# Segliment_Display.net
KiCad netlist of a schematic drawn in EAGLE
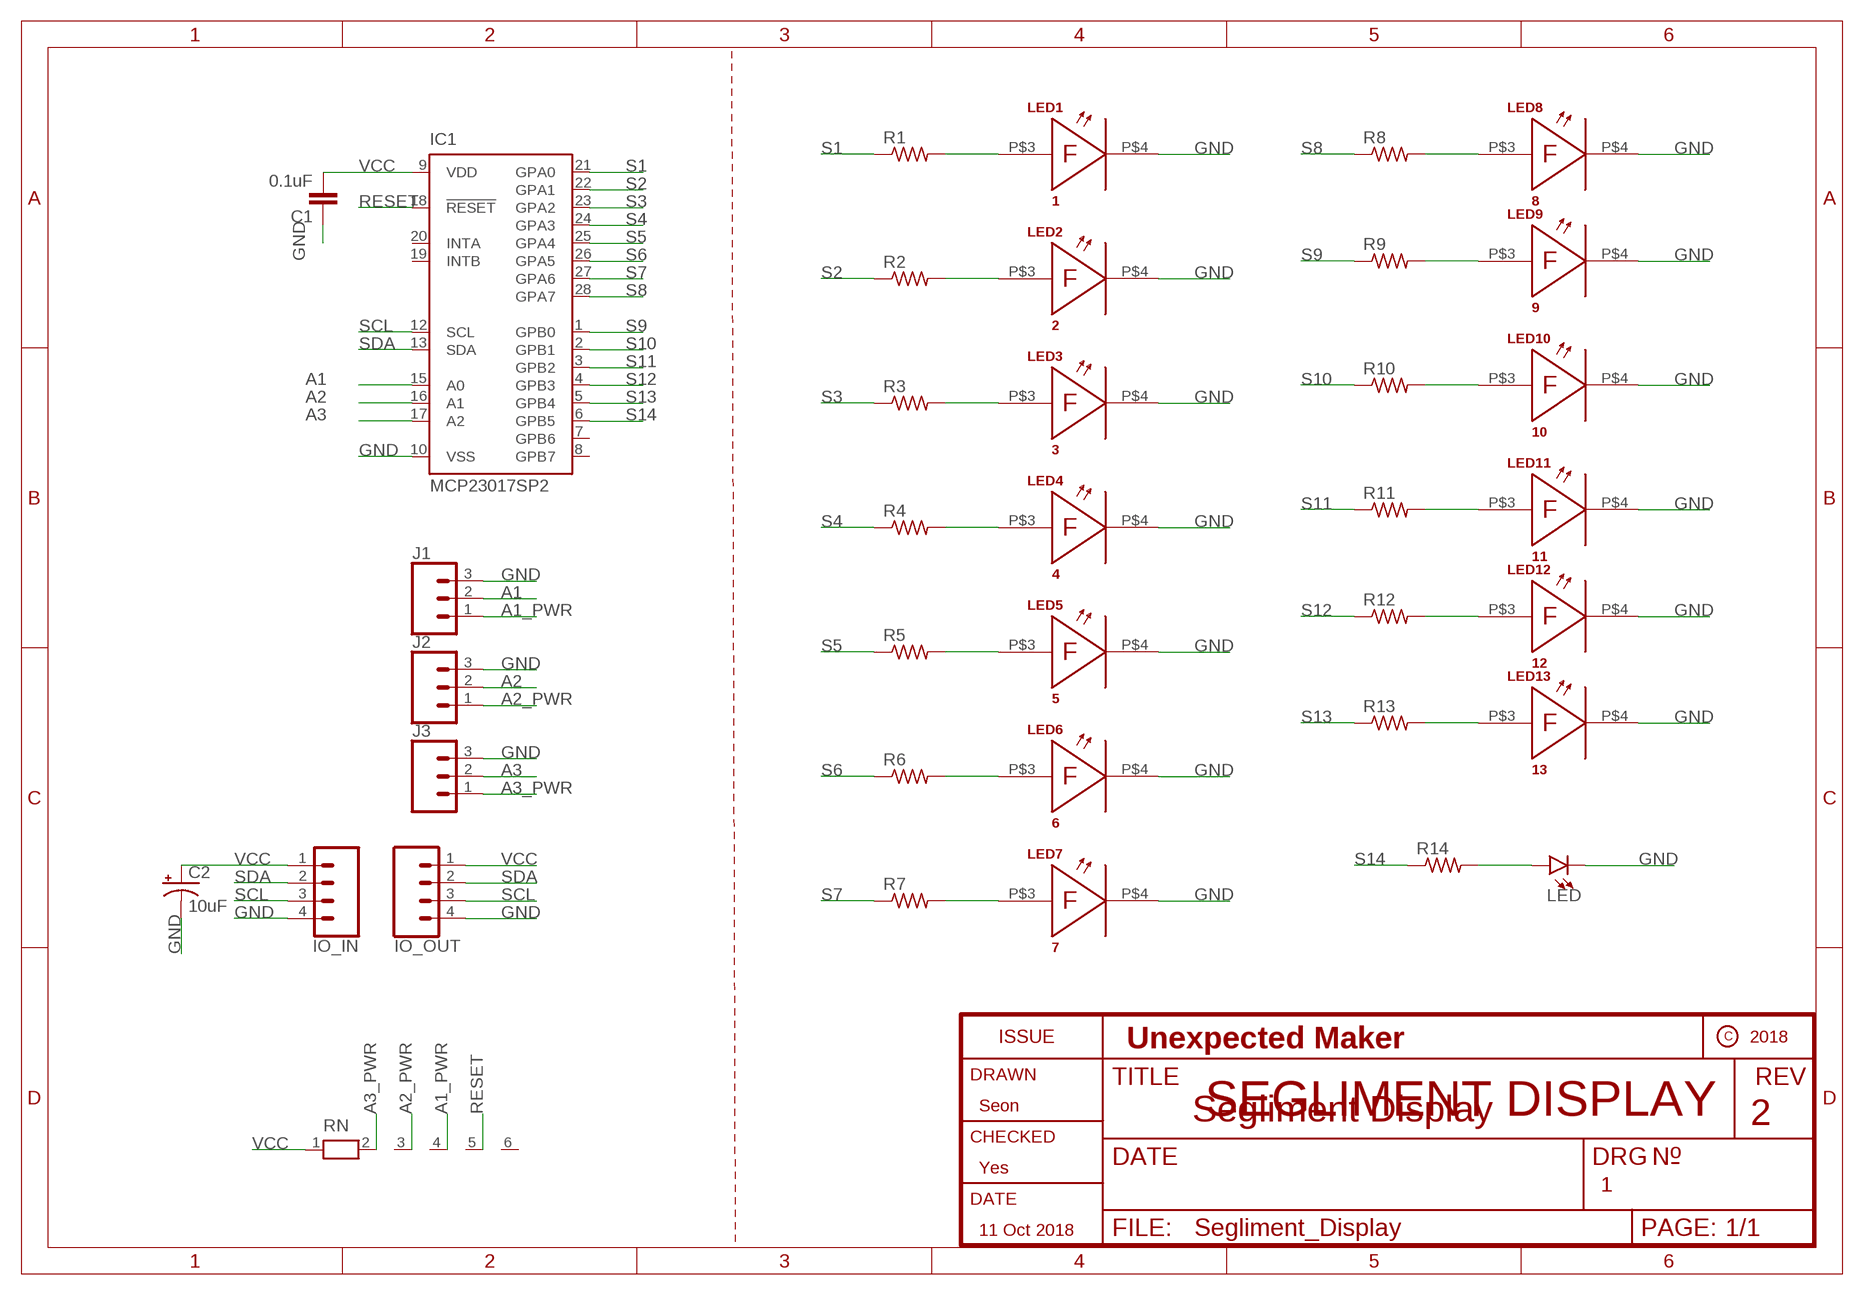
[diagram p0: schematic, sheet 1]

(export (version "E")
  (design (tool "Eeschema 10.0.6"))
  (components
    (comp (ref "C1")
      (value "0.1uF")
      (footprint "eagle-import:CAP-PTH-SMALL-KIT")
      (libsource (lib "eagle-import") (part "0.1UF-KIT-EZ-50V-20%"))
    )
    (comp (ref "C2")
      (value "10uF")
      (footprint "eagle-import:CPOL-RADIAL-2.5MM-5MM")
      (libsource (lib "eagle-import") (part "10UF-POLAR-RADIAL-2.5MM-25V-20%"))
    )
    (comp (ref "IC1")
      (value "MCP23017SP2")
      (footprint "eagle-import:DIL28-3-ROUND")
      (libsource (lib "eagle-import") (part "MCP23017SP2"))
    )
    (comp (ref "IO_IN")
      (value "CONN_041X04_NO_SILK")
      (footprint "eagle-import:1X04_NO_SILK")
      (libsource (lib "eagle-import") (part "CONN_041X04_NO_SILK"))
    )
    (comp (ref "IO_OUT")
      (value "CONN_041X04_NO_SILK")
      (footprint "eagle-import:1X04_NO_SILK")
      (libsource (lib "eagle-import") (part "CONN_041X04_NO_SILK"))
    )
    (comp (ref "J1")
      (value "CONN_031X03_NO_SILK")
      (footprint "eagle-import:1X03_NO_SILK")
      (libsource (lib "eagle-import") (part "CONN_031X03_NO_SILK"))
    )
    (comp (ref "J2")
      (value "CONN_031X03_NO_SILK")
      (footprint "eagle-import:1X03_NO_SILK")
      (libsource (lib "eagle-import") (part "CONN_031X03_NO_SILK"))
    )
    (comp (ref "J3")
      (value "CONN_031X03_NO_SILK")
      (footprint "eagle-import:1X03_NO_SILK")
      (libsource (lib "eagle-import") (part "CONN_031X03_NO_SILK"))
    )
    (comp (ref "LED")
      (value "LED3MM")
      (footprint "eagle-import:LED_3MM")
      (libsource (lib "eagle-import") (part "LED3MM"))
    )
    (comp (ref "LED1")
      (value "1")
      (footprint "eagle-import:RAISED")
      (libsource (lib "eagle-import") (part "LED28-30MMRAISED"))
    )
    (comp (ref "LED2")
      (value "2")
      (footprint "eagle-import:RAISED")
      (libsource (lib "eagle-import") (part "LED28-30MMRAISED"))
    )
    (comp (ref "LED3")
      (value "3")
      (footprint "eagle-import:RAISED")
      (libsource (lib "eagle-import") (part "LED28-30MMRAISED"))
    )
    (comp (ref "LED4")
      (value "4")
      (footprint "eagle-import:RAISED")
      (libsource (lib "eagle-import") (part "LED28-30MMRAISED"))
    )
    (comp (ref "LED5")
      (value "5")
      (footprint "eagle-import:RAISED")
      (libsource (lib "eagle-import") (part "LED28-30MMRAISED"))
    )
    (comp (ref "LED6")
      (value "6")
      (footprint "eagle-import:RAISED")
      (libsource (lib "eagle-import") (part "LED28-30MMRAISED"))
    )
    (comp (ref "LED7")
      (value "7")
      (footprint "eagle-import:RAISED")
      (libsource (lib "eagle-import") (part "LED28-30MMRAISED"))
    )
    (comp (ref "LED8")
      (value "8")
      (footprint "eagle-import:RAISED")
      (libsource (lib "eagle-import") (part "LED28-30MMRAISED"))
    )
    (comp (ref "LED9")
      (value "9")
      (footprint "eagle-import:RAISED")
      (libsource (lib "eagle-import") (part "LED28-30MMRAISED"))
    )
    (comp (ref "LED10")
      (value "10")
      (footprint "eagle-import:RAISED")
      (libsource (lib "eagle-import") (part "LED28-30MMRAISED"))
    )
    (comp (ref "LED11")
      (value "11")
      (footprint "eagle-import:RAISED")
      (libsource (lib "eagle-import") (part "LED28-30MMRAISED"))
    )
    (comp (ref "LED12")
      (value "12")
      (footprint "eagle-import:RAISED")
      (libsource (lib "eagle-import") (part "LED28-30MMRAISED"))
    )
    (comp (ref "LED13")
      (value "13")
      (footprint "eagle-import:RAISED")
      (libsource (lib "eagle-import") (part "LED28-30MMRAISED"))
    )
    (comp (ref "R1")
      (value "R-US_0207/7")
      (footprint "eagle-import:0207_7")
      (libsource (lib "eagle-import") (part "R-US_0207/7"))
    )
    (comp (ref "R2")
      (value "R-US_0207/7")
      (footprint "eagle-import:0207_7")
      (libsource (lib "eagle-import") (part "R-US_0207/7"))
    )
    (comp (ref "R3")
      (value "R-US_0207/7")
      (footprint "eagle-import:0207_7")
      (libsource (lib "eagle-import") (part "R-US_0207/7"))
    )
    (comp (ref "R4")
      (value "R-US_0207/7")
      (footprint "eagle-import:0207_7")
      (libsource (lib "eagle-import") (part "R-US_0207/7"))
    )
    (comp (ref "R5")
      (value "R-US_0207/7")
      (footprint "eagle-import:0207_7")
      (libsource (lib "eagle-import") (part "R-US_0207/7"))
    )
    (comp (ref "R6")
      (value "R-US_0207/7")
      (footprint "eagle-import:0207_7")
      (libsource (lib "eagle-import") (part "R-US_0207/7"))
    )
    (comp (ref "R7")
      (value "R-US_0207/7")
      (footprint "eagle-import:0207_7")
      (libsource (lib "eagle-import") (part "R-US_0207/7"))
    )
    (comp (ref "R8")
      (value "R-US_0207/7")
      (footprint "eagle-import:0207_7")
      (libsource (lib "eagle-import") (part "R-US_0207/7"))
    )
    (comp (ref "R9")
      (value "R-US_0207/7")
      (footprint "eagle-import:0207_7")
      (libsource (lib "eagle-import") (part "R-US_0207/7"))
    )
    (comp (ref "R10")
      (value "R-US_0207/7")
      (footprint "eagle-import:0207_7")
      (libsource (lib "eagle-import") (part "R-US_0207/7"))
    )
    (comp (ref "R11")
      (value "R-US_0207/7")
      (footprint "eagle-import:0207_7")
      (libsource (lib "eagle-import") (part "R-US_0207/7"))
    )
    (comp (ref "R12")
      (value "R-US_0207/7")
      (footprint "eagle-import:0207_7")
      (libsource (lib "eagle-import") (part "R-US_0207/7"))
    )
    (comp (ref "R13")
      (value "R-US_0207/7")
      (footprint "eagle-import:0207_7")
      (libsource (lib "eagle-import") (part "R-US_0207/7"))
    )
    (comp (ref "R14")
      (value "R-US_0207/7")
      (footprint "eagle-import:0207_7")
      (libsource (lib "eagle-import") (part "R-US_0207/7"))
    )
    (comp (ref "RN")
      (value "RN05")
      (footprint "eagle-import:RN-6")
      (libsource (lib "eagle-import") (part "RN05"))
    )
  )
  (nets
    (net (code "1") (name "/A1") (class "Default")
      (node (ref "IC1") (pin "15") (pinfunction "A0_15") (pintype "input"))
      (node (ref "J1") (pin "2") (pinfunction "2_2") (pintype "passive"))
    )
    (net (code "2") (name "/A1_PWR") (class "Default")
      (node (ref "J1") (pin "1") (pinfunction "1_1") (pintype "passive"))
      (node (ref "RN") (pin "4") (pinfunction "4_4") (pintype "passive"))
    )
    (net (code "3") (name "/A2") (class "Default")
      (node (ref "IC1") (pin "16") (pinfunction "A1_16") (pintype "input"))
      (node (ref "J2") (pin "2") (pinfunction "2_2") (pintype "passive"))
    )
    (net (code "4") (name "/A2_PWR") (class "Default")
      (node (ref "J2") (pin "1") (pinfunction "1_1") (pintype "passive"))
      (node (ref "RN") (pin "3") (pinfunction "3_3") (pintype "passive"))
    )
    (net (code "5") (name "/A3") (class "Default")
      (node (ref "IC1") (pin "17") (pinfunction "A2_17") (pintype "input"))
      (node (ref "J3") (pin "2") (pinfunction "2_2") (pintype "passive"))
    )
    (net (code "6") (name "/A3_PWR") (class "Default")
      (node (ref "J3") (pin "1") (pinfunction "1_1") (pintype "passive"))
      (node (ref "RN") (pin "2") (pinfunction "2_2") (pintype "passive"))
    )
    (net (code "7") (name "/GND") (class "Default")
      (node (ref "C1") (pin "1") (pinfunction "1_1") (pintype "passive"))
      (node (ref "C2") (pin "2") (pinfunction "-_2") (pintype "passive"))
      (node (ref "IC1") (pin "10") (pinfunction "VSS_10") (pintype "power_in"))
      (node (ref "IO_IN") (pin "4") (pinfunction "4_4") (pintype "passive"))
      (node (ref "IO_OUT") (pin "4") (pinfunction "4_4") (pintype "passive"))
      (node (ref "J1") (pin "3") (pinfunction "3_3") (pintype "passive"))
      (node (ref "J2") (pin "3") (pinfunction "3_3") (pintype "passive"))
      (node (ref "J3") (pin "3") (pinfunction "3_3") (pintype "passive"))
      (node (ref "LED") (pin "K") (pinfunction "C_K") (pintype "passive"))
      (node (ref "LED1") (pin "P$4") (pinfunction "P$2_P$4") (pintype "bidirectional"))
      (node (ref "LED10") (pin "P$4") (pinfunction "P$2_P$4") (pintype "bidirectional"))
      (node (ref "LED11") (pin "P$4") (pinfunction "P$2_P$4") (pintype "bidirectional"))
      (node (ref "LED12") (pin "P$4") (pinfunction "P$2_P$4") (pintype "bidirectional"))
      (node (ref "LED13") (pin "P$4") (pinfunction "P$2_P$4") (pintype "bidirectional"))
      (node (ref "LED2") (pin "P$4") (pinfunction "P$2_P$4") (pintype "bidirectional"))
      (node (ref "LED3") (pin "P$4") (pinfunction "P$2_P$4") (pintype "bidirectional"))
      (node (ref "LED4") (pin "P$4") (pinfunction "P$2_P$4") (pintype "bidirectional"))
      (node (ref "LED5") (pin "P$4") (pinfunction "P$2_P$4") (pintype "bidirectional"))
      (node (ref "LED6") (pin "P$4") (pinfunction "P$2_P$4") (pintype "bidirectional"))
      (node (ref "LED7") (pin "P$4") (pinfunction "P$2_P$4") (pintype "bidirectional"))
      (node (ref "LED8") (pin "P$4") (pinfunction "P$2_P$4") (pintype "bidirectional"))
      (node (ref "LED9") (pin "P$4") (pinfunction "P$2_P$4") (pintype "bidirectional"))
    )
    (net (code "8") (name "/RESET") (class "Default")
      (node (ref "IC1") (pin "18") (pinfunction "~{RESET}_18") (pintype "input"))
      (node (ref "RN") (pin "5") (pinfunction "5_5") (pintype "passive"))
    )
    (net (code "9") (name "/S1") (class "Default")
      (node (ref "IC1") (pin "21") (pinfunction "GPA0_21") (pintype "bidirectional"))
      (node (ref "R1") (pin "1") (pinfunction "1_1") (pintype "passive"))
    )
    (net (code "10") (name "/S2") (class "Default")
      (node (ref "IC1") (pin "22") (pinfunction "GPA1_22") (pintype "bidirectional"))
      (node (ref "R2") (pin "1") (pinfunction "1_1") (pintype "passive"))
    )
    (net (code "11") (name "/S3") (class "Default")
      (node (ref "IC1") (pin "23") (pinfunction "GPA2_23") (pintype "bidirectional"))
      (node (ref "R3") (pin "1") (pinfunction "1_1") (pintype "passive"))
    )
    (net (code "12") (name "/S4") (class "Default")
      (node (ref "IC1") (pin "24") (pinfunction "GPA3_24") (pintype "bidirectional"))
      (node (ref "R4") (pin "1") (pinfunction "1_1") (pintype "passive"))
    )
    (net (code "13") (name "/S5") (class "Default")
      (node (ref "IC1") (pin "25") (pinfunction "GPA4_25") (pintype "bidirectional"))
      (node (ref "R5") (pin "1") (pinfunction "1_1") (pintype "passive"))
    )
    (net (code "14") (name "/S6") (class "Default")
      (node (ref "IC1") (pin "26") (pinfunction "GPA5_26") (pintype "bidirectional"))
      (node (ref "R6") (pin "1") (pinfunction "1_1") (pintype "passive"))
    )
    (net (code "15") (name "/S7") (class "Default")
      (node (ref "IC1") (pin "27") (pinfunction "GPA6_27") (pintype "bidirectional"))
      (node (ref "R7") (pin "1") (pinfunction "1_1") (pintype "passive"))
    )
    (net (code "16") (name "/S8") (class "Default")
      (node (ref "IC1") (pin "28") (pinfunction "GPA7_28") (pintype "bidirectional"))
      (node (ref "R8") (pin "1") (pinfunction "1_1") (pintype "passive"))
    )
    (net (code "17") (name "/S9") (class "Default")
      (node (ref "IC1") (pin "1") (pinfunction "GPB0_1") (pintype "bidirectional"))
      (node (ref "R9") (pin "1") (pinfunction "1_1") (pintype "passive"))
    )
    (net (code "18") (name "/S10") (class "Default")
      (node (ref "IC1") (pin "2") (pinfunction "GPB1_2") (pintype "bidirectional"))
      (node (ref "R10") (pin "1") (pinfunction "1_1") (pintype "passive"))
    )
    (net (code "19") (name "/S11") (class "Default")
      (node (ref "IC1") (pin "3") (pinfunction "GPB2_3") (pintype "bidirectional"))
      (node (ref "R11") (pin "1") (pinfunction "1_1") (pintype "passive"))
    )
    (net (code "20") (name "/S12") (class "Default")
      (node (ref "IC1") (pin "4") (pinfunction "GPB3_4") (pintype "bidirectional"))
      (node (ref "R12") (pin "1") (pinfunction "1_1") (pintype "passive"))
    )
    (net (code "21") (name "/S13") (class "Default")
      (node (ref "IC1") (pin "5") (pinfunction "GPB4_5") (pintype "bidirectional"))
      (node (ref "R13") (pin "1") (pinfunction "1_1") (pintype "passive"))
    )
    (net (code "22") (name "/S14") (class "Default")
      (node (ref "IC1") (pin "6") (pinfunction "GPB5_6") (pintype "bidirectional"))
      (node (ref "R14") (pin "1") (pinfunction "1_1") (pintype "passive"))
    )
    (net (code "23") (name "/SCL") (class "Default")
      (node (ref "IC1") (pin "12") (pinfunction "SCL_12") (pintype "input"))
      (node (ref "IO_IN") (pin "3") (pinfunction "3_3") (pintype "passive"))
      (node (ref "IO_OUT") (pin "3") (pinfunction "3_3") (pintype "passive"))
    )
    (net (code "24") (name "/SDA") (class "Default")
      (node (ref "IC1") (pin "13") (pinfunction "SDA_13") (pintype "bidirectional"))
      (node (ref "IO_IN") (pin "2") (pinfunction "2_2") (pintype "passive"))
      (node (ref "IO_OUT") (pin "2") (pinfunction "2_2") (pintype "passive"))
    )
    (net (code "25") (name "/VCC") (class "Default")
      (node (ref "C1") (pin "2") (pinfunction "2_2") (pintype "passive"))
      (node (ref "C2") (pin "1") (pinfunction "+_1") (pintype "passive"))
      (node (ref "IC1") (pin "9") (pinfunction "VDD_9") (pintype "power_in"))
      (node (ref "IO_IN") (pin "1") (pinfunction "1_1") (pintype "passive"))
      (node (ref "IO_OUT") (pin "1") (pinfunction "1_1") (pintype "passive"))
      (node (ref "RN") (pin "1") (pinfunction "1_1") (pintype "passive"))
    )
    (net (code "26") (name "Net-(LED-PadA)") (class "Default")
      (node (ref "LED") (pin "A") (pinfunction "A_A") (pintype "passive"))
      (node (ref "R14") (pin "2") (pinfunction "2_2") (pintype "passive"))
    )
    (net (code "27") (name "Net-(LED1-P$1)") (class "Default")
      (node (ref "LED1") (pin "P$3") (pinfunction "P$1_P$3") (pintype "bidirectional"))
      (node (ref "R1") (pin "2") (pinfunction "2_2") (pintype "passive"))
    )
    (net (code "28") (name "Net-(LED2-P$1)") (class "Default")
      (node (ref "LED2") (pin "P$3") (pinfunction "P$1_P$3") (pintype "bidirectional"))
      (node (ref "R2") (pin "2") (pinfunction "2_2") (pintype "passive"))
    )
    (net (code "29") (name "Net-(LED3-P$1)") (class "Default")
      (node (ref "LED3") (pin "P$3") (pinfunction "P$1_P$3") (pintype "bidirectional"))
      (node (ref "R3") (pin "2") (pinfunction "2_2") (pintype "passive"))
    )
    (net (code "30") (name "Net-(LED4-P$1)") (class "Default")
      (node (ref "LED4") (pin "P$3") (pinfunction "P$1_P$3") (pintype "bidirectional"))
      (node (ref "R4") (pin "2") (pinfunction "2_2") (pintype "passive"))
    )
    (net (code "31") (name "Net-(LED5-P$1)") (class "Default")
      (node (ref "LED5") (pin "P$3") (pinfunction "P$1_P$3") (pintype "bidirectional"))
      (node (ref "R5") (pin "2") (pinfunction "2_2") (pintype "passive"))
    )
    (net (code "32") (name "Net-(LED6-P$1)") (class "Default")
      (node (ref "LED6") (pin "P$3") (pinfunction "P$1_P$3") (pintype "bidirectional"))
      (node (ref "R6") (pin "2") (pinfunction "2_2") (pintype "passive"))
    )
    (net (code "33") (name "Net-(LED7-P$1)") (class "Default")
      (node (ref "LED7") (pin "P$3") (pinfunction "P$1_P$3") (pintype "bidirectional"))
      (node (ref "R7") (pin "2") (pinfunction "2_2") (pintype "passive"))
    )
    (net (code "34") (name "Net-(LED8-P$1)") (class "Default")
      (node (ref "LED8") (pin "P$3") (pinfunction "P$1_P$3") (pintype "bidirectional"))
      (node (ref "R8") (pin "2") (pinfunction "2_2") (pintype "passive"))
    )
    (net (code "35") (name "Net-(LED9-P$1)") (class "Default")
      (node (ref "LED9") (pin "P$3") (pinfunction "P$1_P$3") (pintype "bidirectional"))
      (node (ref "R9") (pin "2") (pinfunction "2_2") (pintype "passive"))
    )
    (net (code "36") (name "Net-(LED10-P$1)") (class "Default")
      (node (ref "LED10") (pin "P$3") (pinfunction "P$1_P$3") (pintype "bidirectional"))
      (node (ref "R10") (pin "2") (pinfunction "2_2") (pintype "passive"))
    )
    (net (code "37") (name "Net-(LED11-P$1)") (class "Default")
      (node (ref "LED11") (pin "P$3") (pinfunction "P$1_P$3") (pintype "bidirectional"))
      (node (ref "R11") (pin "2") (pinfunction "2_2") (pintype "passive"))
    )
    (net (code "38") (name "Net-(LED12-P$1)") (class "Default")
      (node (ref "LED12") (pin "P$3") (pinfunction "P$1_P$3") (pintype "bidirectional"))
      (node (ref "R12") (pin "2") (pinfunction "2_2") (pintype "passive"))
    )
    (net (code "39") (name "Net-(LED13-P$1)") (class "Default")
      (node (ref "LED13") (pin "P$3") (pinfunction "P$1_P$3") (pintype "bidirectional"))
      (node (ref "R13") (pin "2") (pinfunction "2_2") (pintype "passive"))
    )
    (net (code "40") (name "unconnected-(IC1-GPB6-Pad7)") (class "Default")
      (node (ref "IC1") (pin "7") (pinfunction "GPB6_7") (pintype "bidirectional"))
    )
    (net (code "41") (name "unconnected-(IC1-GPB7-Pad8)") (class "Default")
      (node (ref "IC1") (pin "8") (pinfunction "GPB7_8") (pintype "bidirectional"))
    )
    (net (code "42") (name "unconnected-(IC1-INTA-Pad20)") (class "Default")
      (node (ref "IC1") (pin "20") (pinfunction "INTA_20") (pintype "output"))
    )
    (net (code "43") (name "unconnected-(IC1-INTB-Pad19)") (class "Default")
      (node (ref "IC1") (pin "19") (pinfunction "INTB_19") (pintype "output"))
    )
    (net (code "44") (name "unconnected-(RN-Pad6)") (class "Default")
      (node (ref "RN") (pin "6") (pinfunction "6_6") (pintype "passive"))
    )
  )
)
